# main.net
KiCad netlist of a schematic drawn in EAGLE
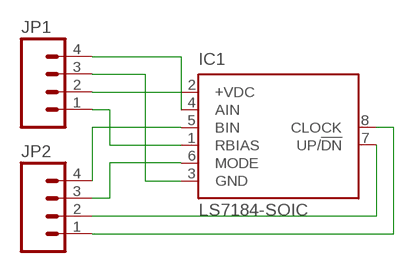
[diagram p0: schematic, sheet 1]

(export (version "E")
  (design (tool "Eeschema 10.0.6"))
  (components
    (comp (ref "IC1")
      (value "LS7184-SOIC")
      (footprint "eagle-import:SOIC08")
      (libsource (lib "eagle-import") (part "LS7184-SOIC"))
    )
    (comp (ref "JP1")
      (value "M04LONGPADS")
      (footprint "eagle-import:1X04_LONGPADS")
      (libsource (lib "eagle-import") (part "M04LONGPADS"))
    )
    (comp (ref "JP2")
      (value "M04LONGPADS")
      (footprint "eagle-import:1X04_LONGPADS")
      (libsource (lib "eagle-import") (part "M04LONGPADS"))
    )
  )
  (nets
    (net (code "1") (name "Net-(IC1-+VDC)") (class "Default")
      (node (ref "IC1") (pin "2") (pinfunction "+VDC_2") (pintype "input"))
      (node (ref "JP1") (pin "2") (pinfunction "2_2") (pintype "passive"))
    )
    (net (code "2") (name "Net-(IC1-AIN)") (class "Default")
      (node (ref "IC1") (pin "4") (pinfunction "AIN_4") (pintype "input"))
      (node (ref "JP1") (pin "4") (pinfunction "4_4") (pintype "passive"))
    )
    (net (code "3") (name "Net-(IC1-BIN)") (class "Default")
      (node (ref "IC1") (pin "5") (pinfunction "BIN_5") (pintype "input"))
      (node (ref "JP2") (pin "4") (pinfunction "4_4") (pintype "passive"))
    )
    (net (code "4") (name "Net-(IC1-CLOCK)") (class "Default")
      (node (ref "IC1") (pin "8") (pinfunction "CLOCK_8") (pintype "input"))
      (node (ref "JP2") (pin "1") (pinfunction "1_1") (pintype "passive"))
    )
    (net (code "5") (name "Net-(IC1-GND)") (class "Default")
      (node (ref "IC1") (pin "3") (pinfunction "GND_3") (pintype "power_in"))
      (node (ref "JP1") (pin "3") (pinfunction "3_3") (pintype "passive"))
    )
    (net (code "6") (name "Net-(IC1-MODE)") (class "Default")
      (node (ref "IC1") (pin "6") (pinfunction "MODE_6") (pintype "input"))
      (node (ref "JP2") (pin "3") (pinfunction "3_3") (pintype "passive"))
    )
    (net (code "7") (name "Net-(IC1-RBIAS)") (class "Default")
      (node (ref "IC1") (pin "1") (pinfunction "RBIAS_1") (pintype "input"))
      (node (ref "JP1") (pin "1") (pinfunction "1_1") (pintype "passive"))
    )
    (net (code "8") (name "Net-(IC1-UP{slash}~{DN})") (class "Default")
      (node (ref "IC1") (pin "7") (pinfunction "UP/~{DN}_7") (pintype "input"))
      (node (ref "JP2") (pin "2") (pinfunction "2_2") (pintype "passive"))
    )
  )
)
